# audio.net
KiCad netlist of a schematic drawn in Altium Designer
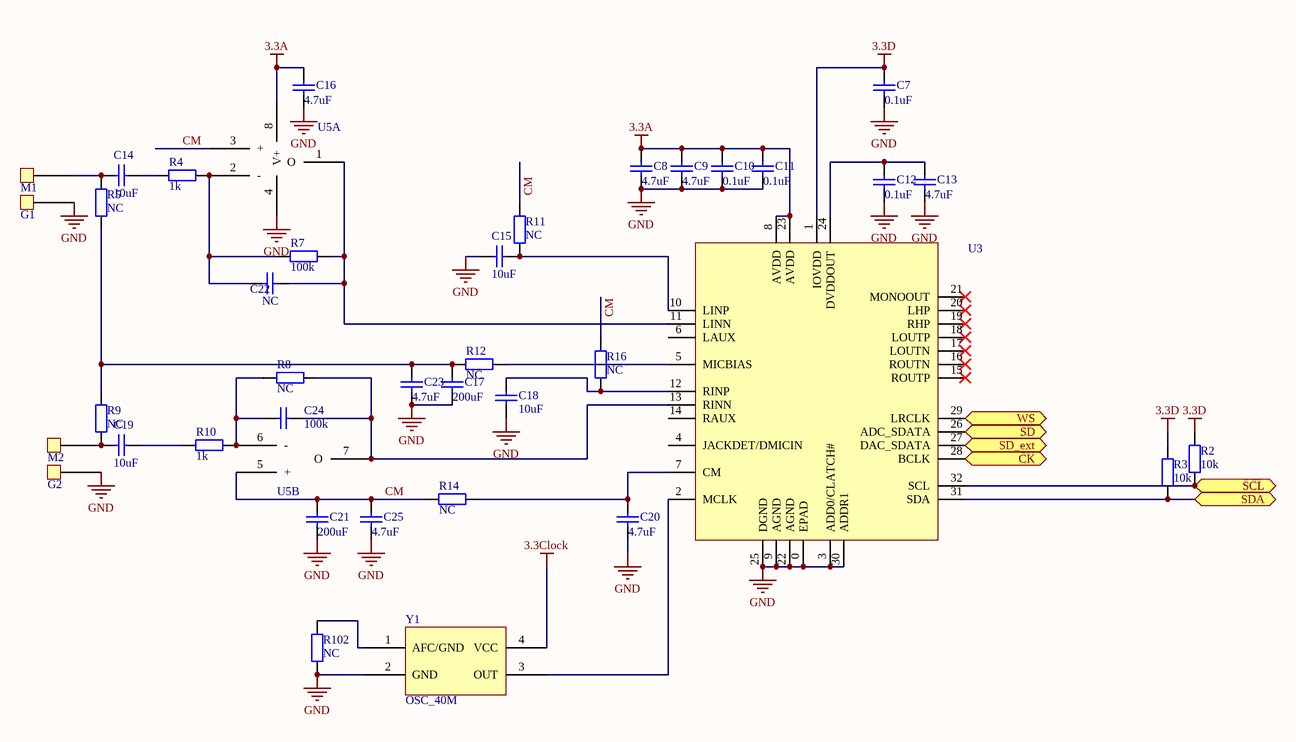
[diagram p0: audio.SchDoc]

(export (version "E")
  (design (tool "Eeschema 10.0.6"))
  (components
    (comp (ref "C7")
      (value "0.1uF")
      (footprint "0402")
      (description "Capacitor")
      (fields (field (name "PUBLISHER") "Altium Limited"))
      (libsource (lib "RTC6705") (part "Cap"))
    )
    (comp (ref "C8")
      (value "4.7uF")
      (footprint "0805")
      (description "Capacitor")
      (fields (field (name "PUBLISHER") "Altium Limited"))
      (libsource (lib "RTC6705") (part "Cap"))
    )
    (comp (ref "C9")
      (value "4.7uF")
      (footprint "0805")
      (description "Capacitor")
      (fields (field (name "PUBLISHER") "Altium Limited"))
      (libsource (lib "RTC6705") (part "Cap"))
    )
    (comp (ref "C10")
      (value "0.1uF")
      (footprint "0402")
      (description "Capacitor")
      (fields (field (name "PUBLISHER") "Altium Limited"))
      (libsource (lib "RTC6705") (part "Cap"))
    )
    (comp (ref "C11")
      (value "0.1uF")
      (footprint "0402")
      (description "Capacitor")
      (fields (field (name "PUBLISHER") "Altium Limited"))
      (libsource (lib "RTC6705") (part "Cap"))
    )
    (comp (ref "C12")
      (value "0.1uF")
      (footprint "0402")
      (description "Capacitor")
      (fields (field (name "PUBLISHER") "Altium Limited"))
      (libsource (lib "RTC6705") (part "Cap"))
    )
    (comp (ref "C13")
      (value "4.7uF")
      (footprint "0805")
      (description "Capacitor")
      (fields (field (name "PUBLISHER") "Altium Limited"))
      (libsource (lib "RTC6705") (part "Cap"))
    )
    (comp (ref "C14")
      (value "10uF")
      (footprint "0805")
      (description "Capacitor")
      (fields (field (name "PUBLISHER") "Altium Limited"))
      (libsource (lib "RTC6705") (part "Cap"))
    )
    (comp (ref "C15")
      (value "10uF")
      (footprint "0805")
      (description "Capacitor")
      (fields (field (name "PUBLISHER") "Altium Limited"))
      (libsource (lib "RTC6705") (part "Cap"))
    )
    (comp (ref "C16")
      (value "4.7uF")
      (footprint "0402")
      (description "Capacitor")
      (fields (field (name "PUBLISHER") "Altium Limited"))
      (libsource (lib "RTC6705") (part "Cap"))
    )
    (comp (ref "C17")
      (value "200uF")
      (footprint "1210")
      (description "Capacitor")
      (fields (field (name "PUBLISHER") "Altium Limited"))
      (libsource (lib "RTC6705") (part "Cap"))
    )
    (comp (ref "C18")
      (value "10uF")
      (footprint "0805")
      (description "Capacitor")
      (fields (field (name "PUBLISHER") "Altium Limited"))
      (libsource (lib "RTC6705") (part "Cap"))
    )
    (comp (ref "C19")
      (value "10uF")
      (footprint "0805")
      (description "Capacitor")
      (fields (field (name "PUBLISHER") "Altium Limited"))
      (libsource (lib "RTC6705") (part "Cap"))
    )
    (comp (ref "C20")
      (value "4.7uF")
      (footprint "0805")
      (description "Capacitor")
      (fields (field (name "PUBLISHER") "Altium Limited"))
      (libsource (lib "RTC6705") (part "Cap"))
    )
    (comp (ref "C21")
      (value "200uF")
      (footprint "1210")
      (description "Capacitor")
      (fields (field (name "PUBLISHER") "Altium Limited"))
      (libsource (lib "RTC6705") (part "Cap"))
    )
    (comp (ref "C22")
      (value "NC")
      (footprint "0402")
      (description "Capacitor")
      (fields (field (name "PUBLISHER") "Altium Limited"))
      (libsource (lib "RTC6705") (part "Cap"))
    )
    (comp (ref "C23")
      (value "4.7uF")
      (footprint "0805")
      (description "Capacitor")
      (fields (field (name "PUBLISHER") "Altium Limited"))
      (libsource (lib "RTC6705") (part "Cap"))
    )
    (comp (ref "C24")
      (value "100k")
      (footprint "0402")
      (description "Capacitor")
      (fields (field (name "PUBLISHER") "Altium Limited"))
      (libsource (lib "RTC6705") (part "Cap"))
    )
    (comp (ref "C25")
      (value "4.7uF")
      (footprint "0805")
      (description "Capacitor")
      (fields (field (name "PUBLISHER") "Altium Limited"))
      (libsource (lib "RTC6705") (part "Cap"))
    )
    (comp (ref "G1") (value "TestPad") (footprint "TestPad") (libsource (lib "sch") (part "TestPad")))
    (comp (ref "G2") (value "TestPad") (footprint "TestPad") (libsource (lib "sch") (part "TestPad")))
    (comp (ref "M1") (value "TestPad") (footprint "TestPad") (libsource (lib "sch") (part "TestPad")))
    (comp (ref "M2") (value "TestPad") (footprint "TestPad") (libsource (lib "sch") (part "TestPad")))
    (comp (ref "R2")
      (value "10k")
      (footprint "0402")
      (description "Resistor")
      (fields (field (name "Comment") "Res2") (field (name "PUBLISHER") "Altium Limited"))
      (libsource (lib "RTC6705") (part "Res2"))
    )
    (comp (ref "R3")
      (value "10k")
      (footprint "0402")
      (description "Resistor")
      (fields (field (name "Comment") "Res2") (field (name "PUBLISHER") "Altium Limited"))
      (libsource (lib "RTC6705") (part "Res2"))
    )
    (comp (ref "R4")
      (value "1k")
      (footprint "0402")
      (description "Resistor")
      (fields (field (name "PUBLISHER") "Altium Limited"))
      (libsource (lib "Miscellaneous Devices") (part "Res2"))
    )
    (comp (ref "R5")
      (value "NC")
      (footprint "0402")
      (description "Resistor")
      (fields (field (name "PUBLISHER") "Altium Limited"))
      (libsource (lib "") (part "Res2_1"))
    )
    (comp (ref "R7")
      (value "100k")
      (footprint "0402")
      (description "Resistor")
      (fields (field (name "PUBLISHER") "Altium Limited"))
      (libsource (lib "Miscellaneous Devices") (part "Res2"))
    )
    (comp (ref "R8")
      (value "NC")
      (footprint "0402")
      (description "Resistor")
      (fields (field (name "PUBLISHER") "Altium Limited"))
      (libsource (lib "Miscellaneous Devices") (part "Res2"))
    )
    (comp (ref "R9")
      (value "NC")
      (footprint "0402")
      (description "Resistor")
      (fields (field (name "PUBLISHER") "Altium Limited"))
      (libsource (lib "") (part "Res2_1"))
    )
    (comp (ref "R10")
      (value "1k")
      (footprint "0402")
      (description "Resistor")
      (fields (field (name "PUBLISHER") "Altium Limited"))
      (libsource (lib "Miscellaneous Devices") (part "Res2"))
    )
    (comp (ref "R11")
      (value "NC")
      (footprint "0402")
      (description "Resistor")
      (fields (field (name "PUBLISHER") "Altium Limited"))
      (libsource (lib "") (part "Res2_2"))
    )
    (comp (ref "R12")
      (value "NC")
      (footprint "0402")
      (description "Resistor")
      (fields (field (name "PUBLISHER") "Altium Limited"))
      (libsource (lib "") (part "Res2_3"))
    )
    (comp (ref "R14")
      (value "NC")
      (footprint "0402")
      (description "Resistor")
      (fields (field (name "PUBLISHER") "Altium Limited"))
      (libsource (lib "") (part "Res2_3"))
    )
    (comp (ref "R16")
      (value "NC")
      (footprint "0402")
      (description "Resistor")
      (fields (field (name "PUBLISHER") "Altium Limited"))
      (libsource (lib "") (part "Res2_2"))
    )
    (comp (ref "R102")
      (value "NC")
      (footprint "0402")
      (description "Resistor")
      (fields (field (name "PUBLISHER") "Altium Limited"))
      (libsource (lib "") (part "Res2_2"))
    )
    (comp (ref "U3") (value "ADAU1761") (footprint "ADAU1761") (libsource (lib "ADAU1761") (part "ADAU1761")))
    (comp (ref "U5") (value "OP-2") (footprint "SO8") (libsource (lib "ADAU1761") (part "OP-2")))
    (comp (ref "Y1") (value "OSC_40M") (footprint "TXC_7Q") (libsource (lib "F4SDR") (part "OSC_40M")))
  )
  (nets
    (net (code "1") (name "/CK") (class "Default")
      (node (ref "U3") (pin "28") (pinfunction "BCLK_28") (pintype "passive"))
    )
    (net (code "2") (name "/CM") (class "Default")
      (node (ref "C21") (pin "2") (pinfunction "2_2") (pintype "passive"))
      (node (ref "C25") (pin "2") (pinfunction "2_2") (pintype "passive"))
      (node (ref "R11") (pin "1") (pinfunction "1_1") (pintype "passive"))
      (node (ref "R14") (pin "2") (pinfunction "2_2") (pintype "passive"))
      (node (ref "R16") (pin "1") (pinfunction "1_1") (pintype "passive"))
      (node (ref "U5") (pin "3") (pinfunction "+_3") (pintype "passive"))
      (node (ref "U5") (pin "5") (pinfunction "+_5") (pintype "passive"))
    )
    (net (code "3") (name "/SCL") (class "Default")
      (node (ref "R2") (pin "1") (pinfunction "1_1") (pintype "passive"))
      (node (ref "U3") (pin "32") (pinfunction "SCL_32") (pintype "passive"))
    )
    (net (code "4") (name "/SD") (class "Default")
      (node (ref "U3") (pin "26") (pinfunction "ADC_SDATA_26") (pintype "passive"))
    )
    (net (code "5") (name "/SDA") (class "Default")
      (node (ref "R3") (pin "1") (pinfunction "1_1") (pintype "passive"))
      (node (ref "U3") (pin "31") (pinfunction "SDA_31") (pintype "passive"))
    )
    (net (code "6") (name "/SD_ext") (class "Default")
      (node (ref "U3") (pin "27") (pinfunction "DAC_SDATA_27") (pintype "passive"))
    )
    (net (code "7") (name "/WS") (class "Default")
      (node (ref "U3") (pin "29") (pinfunction "LRCLK_29") (pintype "passive"))
    )
    (net (code "8") (name "3.3A") (class "Default")
      (node (ref "C10") (pin "2") (pinfunction "2_2") (pintype "passive"))
      (node (ref "C11") (pin "2") (pinfunction "2_2") (pintype "passive"))
      (node (ref "C16") (pin "2") (pinfunction "2_2") (pintype "passive"))
      (node (ref "C8") (pin "2") (pinfunction "2_2") (pintype "passive"))
      (node (ref "C9") (pin "2") (pinfunction "2_2") (pintype "passive"))
      (node (ref "U3") (pin "23") (pinfunction "AVDD_23") (pintype "passive"))
      (node (ref "U3") (pin "8") (pinfunction "AVDD_8") (pintype "passive"))
      (node (ref "U5") (pin "8") (pinfunction "V+_8") (pintype "passive"))
    )
    (net (code "9") (name "3.3Clock") (class "Default")
      (node (ref "Y1") (pin "4") (pinfunction "VCC_4") (pintype "passive"))
    )
    (net (code "10") (name "3.3D") (class "Default")
      (node (ref "C7") (pin "2") (pinfunction "2_2") (pintype "passive"))
      (node (ref "R2") (pin "2") (pinfunction "2_2") (pintype "passive"))
      (node (ref "R3") (pin "2") (pinfunction "2_2") (pintype "passive"))
      (node (ref "U3") (pin "1") (pinfunction "IOVDD_1") (pintype "passive"))
    )
    (net (code "11") (name "GND") (class "Default")
      (node (ref "C10") (pin "1") (pinfunction "1_1") (pintype "passive"))
      (node (ref "C11") (pin "1") (pinfunction "1_1") (pintype "passive"))
      (node (ref "C12") (pin "1") (pinfunction "1_1") (pintype "passive"))
      (node (ref "C13") (pin "1") (pinfunction "1_1") (pintype "passive"))
      (node (ref "C15") (pin "2") (pinfunction "2_2") (pintype "passive"))
      (node (ref "C16") (pin "1") (pinfunction "1_1") (pintype "passive"))
      (node (ref "C17") (pin "1") (pinfunction "1_1") (pintype "passive"))
      (node (ref "C18") (pin "1") (pinfunction "1_1") (pintype "passive"))
      (node (ref "C20") (pin "1") (pinfunction "1_1") (pintype "passive"))
      (node (ref "C21") (pin "1") (pinfunction "1_1") (pintype "passive"))
      (node (ref "C23") (pin "1") (pinfunction "1_1") (pintype "passive"))
      (node (ref "C25") (pin "1") (pinfunction "1_1") (pintype "passive"))
      (node (ref "C7") (pin "1") (pinfunction "1_1") (pintype "passive"))
      (node (ref "C8") (pin "1") (pinfunction "1_1") (pintype "passive"))
      (node (ref "C9") (pin "1") (pinfunction "1_1") (pintype "passive"))
      (node (ref "G1") (pin "1") (pinfunction "3_1") (pintype "passive"))
      (node (ref "G2") (pin "1") (pinfunction "3_1") (pintype "passive"))
      (node (ref "R102") (pin "2") (pinfunction "2_2") (pintype "passive"))
      (node (ref "U3") (pin "0") (pinfunction "EPAD_0") (pintype "passive"))
      (node (ref "U3") (pin "22") (pinfunction "AGND_22") (pintype "passive"))
      (node (ref "U3") (pin "25") (pinfunction "DGND_25") (pintype "passive"))
      (node (ref "U3") (pin "3") (pinfunction "ADD0/CLATCH#_3") (pintype "passive"))
      (node (ref "U3") (pin "30") (pinfunction "ADDR1_30") (pintype "passive"))
      (node (ref "U3") (pin "9") (pinfunction "AGND_9") (pintype "passive"))
      (node (ref "U5") (pin "4") (pinfunction "5_4") (pintype "passive"))
      (node (ref "Y1") (pin "2") (pinfunction "GND_2") (pintype "passive"))
    )
    (net (code "12") (name "Net-(C14-Pad1)") (class "Default")
      (node (ref "C14") (pin "1") (pinfunction "1_1") (pintype "passive"))
      (node (ref "R4") (pin "1") (pinfunction "1_1") (pintype "passive"))
    )
    (net (code "13") (name "Net-(C17-Pad2)") (class "Default")
      (node (ref "C17") (pin "2") (pinfunction "2_2") (pintype "passive"))
      (node (ref "C23") (pin "2") (pinfunction "2_2") (pintype "passive"))
      (node (ref "R12") (pin "2") (pinfunction "2_2") (pintype "passive"))
      (node (ref "R5") (pin "1") (pinfunction "1_1") (pintype "passive"))
      (node (ref "R9") (pin "2") (pinfunction "2_2") (pintype "passive"))
    )
    (net (code "14") (name "Net-(C19-Pad1)") (class "Default")
      (node (ref "C19") (pin "1") (pinfunction "1_1") (pintype "passive"))
      (node (ref "R10") (pin "1") (pinfunction "1_1") (pintype "passive"))
    )
    (net (code "15") (name "Net-(M1-3)") (class "Default")
      (node (ref "C14") (pin "2") (pinfunction "2_2") (pintype "passive"))
      (node (ref "M1") (pin "1") (pinfunction "3_1") (pintype "passive"))
      (node (ref "R5") (pin "2") (pinfunction "2_2") (pintype "passive"))
    )
    (net (code "16") (name "Net-(M2-3)") (class "Default")
      (node (ref "C19") (pin "2") (pinfunction "2_2") (pintype "passive"))
      (node (ref "M2") (pin "1") (pinfunction "3_1") (pintype "passive"))
      (node (ref "R9") (pin "1") (pinfunction "1_1") (pintype "passive"))
    )
    (net (code "17") (name "Net-(U3-CM)") (class "Default")
      (node (ref "C20") (pin "2") (pinfunction "2_2") (pintype "passive"))
      (node (ref "R14") (pin "1") (pinfunction "1_1") (pintype "passive"))
      (node (ref "U3") (pin "7") (pinfunction "CM_7") (pintype "passive"))
    )
    (net (code "18") (name "Net-(U3-DVDDOUT)") (class "Default")
      (node (ref "C12") (pin "2") (pinfunction "2_2") (pintype "passive"))
      (node (ref "C13") (pin "2") (pinfunction "2_2") (pintype "passive"))
      (node (ref "U3") (pin "24") (pinfunction "DVDDOUT_24") (pintype "passive"))
    )
    (net (code "19") (name "Net-(U3-LINN)") (class "Default")
      (node (ref "C22") (pin "1") (pinfunction "1_1") (pintype "passive"))
      (node (ref "R7") (pin "2") (pinfunction "2_2") (pintype "passive"))
      (node (ref "U3") (pin "11") (pinfunction "LINN_11") (pintype "passive"))
      (node (ref "U5") (pin "1") (pinfunction "O_1") (pintype "passive"))
    )
    (net (code "20") (name "Net-(U3-LINP)") (class "Default")
      (node (ref "C15") (pin "1") (pinfunction "1_1") (pintype "passive"))
      (node (ref "R11") (pin "2") (pinfunction "2_2") (pintype "passive"))
      (node (ref "U3") (pin "10") (pinfunction "LINP_10") (pintype "passive"))
    )
    (net (code "21") (name "Net-(U3-MCLK)") (class "Default")
      (node (ref "U3") (pin "2") (pinfunction "MCLK_2") (pintype "passive"))
      (node (ref "Y1") (pin "3") (pinfunction "OUT_3") (pintype "passive"))
    )
    (net (code "22") (name "Net-(U3-MICBIAS)") (class "Default")
      (node (ref "R12") (pin "1") (pinfunction "1_1") (pintype "passive"))
      (node (ref "U3") (pin "5") (pinfunction "MICBIAS_5") (pintype "passive"))
    )
    (net (code "23") (name "Net-(U3-RINN)") (class "Default")
      (node (ref "C24") (pin "1") (pinfunction "1_1") (pintype "passive"))
      (node (ref "R8") (pin "2") (pinfunction "2_2") (pintype "passive"))
      (node (ref "U3") (pin "13") (pinfunction "RINN_13") (pintype "passive"))
      (node (ref "U5") (pin "7") (pinfunction "O_7") (pintype "passive"))
    )
    (net (code "24") (name "Net-(U3-RINP)") (class "Default")
      (node (ref "C18") (pin "2") (pinfunction "2_2") (pintype "passive"))
      (node (ref "R16") (pin "2") (pinfunction "2_2") (pintype "passive"))
      (node (ref "U3") (pin "12") (pinfunction "RINP_12") (pintype "passive"))
    )
    (net (code "25") (name "Net-(U5A--)") (class "Default")
      (node (ref "C22") (pin "2") (pinfunction "2_2") (pintype "passive"))
      (node (ref "R4") (pin "2") (pinfunction "2_2") (pintype "passive"))
      (node (ref "R7") (pin "1") (pinfunction "1_1") (pintype "passive"))
      (node (ref "U5") (pin "2") (pinfunction "-_2") (pintype "passive"))
    )
    (net (code "26") (name "Net-(U5B--)") (class "Default")
      (node (ref "C24") (pin "2") (pinfunction "2_2") (pintype "passive"))
      (node (ref "R10") (pin "2") (pinfunction "2_2") (pintype "passive"))
      (node (ref "R8") (pin "1") (pinfunction "1_1") (pintype "passive"))
      (node (ref "U5") (pin "6") (pinfunction "-_6") (pintype "passive"))
    )
    (net (code "27") (name "Net-(Y1-AFC{slash}GND)") (class "Default")
      (node (ref "R102") (pin "1") (pinfunction "1_1") (pintype "passive"))
      (node (ref "Y1") (pin "1") (pinfunction "AFC/GND_1") (pintype "passive"))
    )
    (net (code "28") (name "unconnected-(U3-JACKDET{slash}DMICIN-Pad4)") (class "Default")
      (node (ref "U3") (pin "4") (pinfunction "JACKDET/DMICIN_4") (pintype "passive"))
    )
    (net (code "29") (name "unconnected-(U3-LAUX-Pad6)") (class "Default")
      (node (ref "U3") (pin "6") (pinfunction "LAUX_6") (pintype "passive"))
    )
    (net (code "30") (name "unconnected-(U3-LHP-Pad20)") (class "Default")
      (node (ref "U3") (pin "20") (pinfunction "LHP_20") (pintype "passive+no_connect"))
    )
    (net (code "31") (name "unconnected-(U3-LOUTN-Pad17)") (class "Default")
      (node (ref "U3") (pin "17") (pinfunction "LOUTN_17") (pintype "passive+no_connect"))
    )
    (net (code "32") (name "unconnected-(U3-LOUTP-Pad18)") (class "Default")
      (node (ref "U3") (pin "18") (pinfunction "LOUTP_18") (pintype "passive+no_connect"))
    )
    (net (code "33") (name "unconnected-(U3-MONOOUT-Pad21)") (class "Default")
      (node (ref "U3") (pin "21") (pinfunction "MONOOUT_21") (pintype "passive+no_connect"))
    )
    (net (code "34") (name "unconnected-(U3-RAUX-Pad14)") (class "Default")
      (node (ref "U3") (pin "14") (pinfunction "RAUX_14") (pintype "passive"))
    )
    (net (code "35") (name "unconnected-(U3-RHP-Pad19)") (class "Default")
      (node (ref "U3") (pin "19") (pinfunction "RHP_19") (pintype "passive+no_connect"))
    )
    (net (code "36") (name "unconnected-(U3-ROUTN-Pad16)") (class "Default")
      (node (ref "U3") (pin "16") (pinfunction "ROUTN_16") (pintype "passive+no_connect"))
    )
    (net (code "37") (name "unconnected-(U3-ROUTP-Pad15)") (class "Default")
      (node (ref "U3") (pin "15") (pinfunction "ROUTP_15") (pintype "passive+no_connect"))
    )
  )
)
